# connection.net
KiCad netlist of a schematic drawn in Altium Designer
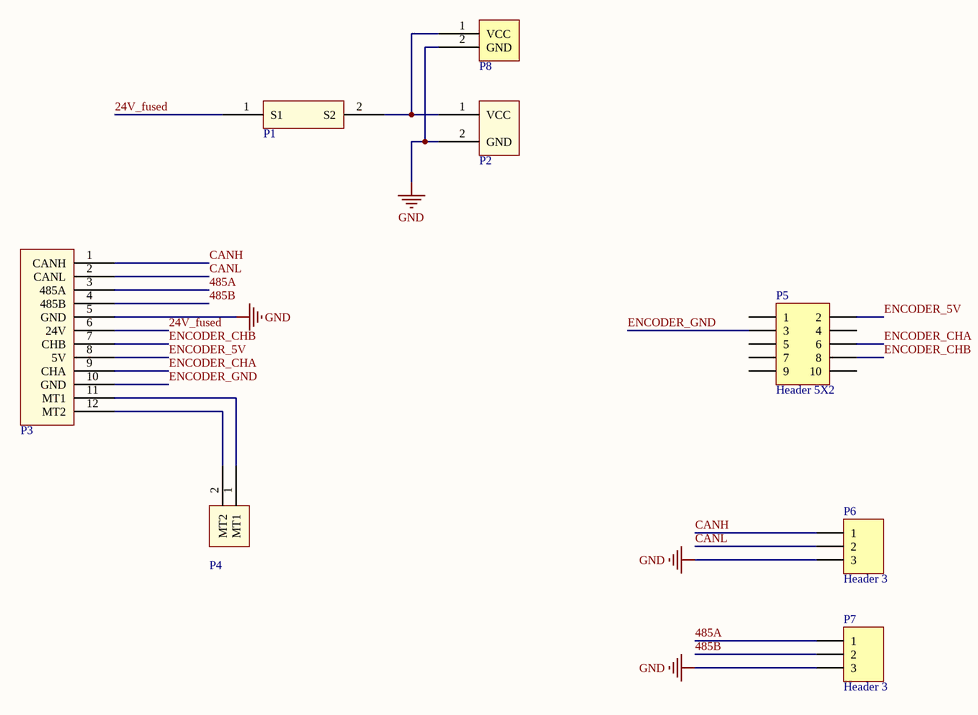
[diagram p0: connection.SchDoc]

(export (version "E")
  (design (tool "Eeschema 10.0.6"))
  (components
    (comp (ref "P1")
      (value "Car Fuse")
      (footprint "car_fuse")
      (libsource (lib "car_fuse") (part "Component_1"))
    )
    (comp (ref "P2")
      (value "big Pin power port")
      (footprint "bigPin_power_port")
      (libsource (lib "bigPin_power_port") (part "big Pin power port"))
    )
    (comp (ref "P3")
      (value "Robo Module Connector")
      (footprint "robomoduleConnector")
      (libsource (lib "robo_module_connector") (part "robomoduleConnector"))
    )
    (comp (ref "P4")
      (value "KF762-p_connector")
      (footprint "KF762")
      (libsource (lib "KF762connector") (part "KF762-p_connector"))
    )
    (comp (ref "P5")
      (value "Header 5X2")
      (footprint "HDR2X5")
      (description "Header, 5-Pin, Dual row")
      (fields (field (name "PUBLISHER") "Altium Limited"))
      (libsource (lib "Miscellaneous Connectors") (part "Header 5X2"))
    )
    (comp (ref "P6")
      (value "Header 3")
      (footprint "HDR1X3")
      (description "Header, 3-Pin")
      (fields (field (name "PUBLISHER") "Altium Limited"))
      (libsource (lib "Miscellaneous Connectors") (part "Header 3"))
    )
    (comp (ref "P7")
      (value "Header 3")
      (footprint "HDR1X3")
      (description "Header, 3-Pin")
      (fields (field (name "PUBLISHER") "Altium Limited"))
      (libsource (lib "Miscellaneous Connectors") (part "Header 3"))
    )
    (comp (ref "P8")
      (value "5557 Connector")
      (footprint "5557_connector")
      (libsource (lib "5557 connector") (part "5557_connector"))
    )
  )
  (nets
    (net (code "1") (name "/24V_fused") (class "Default")
      (node (ref "P1") (pin "1") (pinfunction "S1_1") (pintype "passive"))
      (node (ref "P3") (pin "6") (pinfunction "24V_6") (pintype "passive"))
    )
    (net (code "2") (name "/485A") (class "Default")
      (node (ref "P3") (pin "3") (pinfunction "485A_3") (pintype "passive"))
      (node (ref "P7") (pin "1") (pinfunction "1_1") (pintype "passive"))
    )
    (net (code "3") (name "/485B") (class "Default")
      (node (ref "P3") (pin "4") (pinfunction "485B_4") (pintype "passive"))
      (node (ref "P7") (pin "2") (pinfunction "2_2") (pintype "passive"))
    )
    (net (code "4") (name "/CANH") (class "Default")
      (node (ref "P3") (pin "1") (pinfunction "CANH_1") (pintype "passive"))
      (node (ref "P6") (pin "1") (pinfunction "1_1") (pintype "passive"))
    )
    (net (code "5") (name "/CANL") (class "Default")
      (node (ref "P3") (pin "2") (pinfunction "CANL_2") (pintype "passive"))
      (node (ref "P6") (pin "2") (pinfunction "2_2") (pintype "passive"))
    )
    (net (code "6") (name "/ENCODER_5V") (class "Default")
      (node (ref "P3") (pin "8") (pinfunction "5V_8") (pintype "passive"))
      (node (ref "P5") (pin "2") (pinfunction "2_2") (pintype "passive"))
    )
    (net (code "7") (name "/ENCODER_CHA") (class "Default")
      (node (ref "P3") (pin "9") (pinfunction "CHA_9") (pintype "passive"))
      (node (ref "P5") (pin "6") (pinfunction "6_6") (pintype "passive"))
    )
    (net (code "8") (name "/ENCODER_CHB") (class "Default")
      (node (ref "P3") (pin "7") (pinfunction "CHB_7") (pintype "passive"))
      (node (ref "P5") (pin "8") (pinfunction "8_8") (pintype "passive"))
    )
    (net (code "9") (name "/ENCODER_GND") (class "Default")
      (node (ref "P3") (pin "10") (pinfunction "GND_10") (pintype "passive"))
      (node (ref "P5") (pin "3") (pinfunction "3_3") (pintype "passive"))
    )
    (net (code "10") (name "GND") (class "Default")
      (node (ref "P2") (pin "2") (pinfunction "GND_2") (pintype "passive"))
      (node (ref "P3") (pin "5") (pinfunction "GND_5") (pintype "passive"))
      (node (ref "P6") (pin "3") (pinfunction "3_3") (pintype "passive"))
      (node (ref "P7") (pin "3") (pinfunction "3_3") (pintype "passive"))
      (node (ref "P8") (pin "2") (pinfunction "GND_2") (pintype "passive"))
    )
    (net (code "11") (name "Net-(P1-S2)") (class "Default")
      (node (ref "P1") (pin "2") (pinfunction "S2_2") (pintype "passive"))
      (node (ref "P2") (pin "1") (pinfunction "VCC_1") (pintype "passive"))
      (node (ref "P8") (pin "1") (pinfunction "VCC_1") (pintype "passive"))
    )
    (net (code "12") (name "Net-(P3-MT1)") (class "Default")
      (node (ref "P3") (pin "11") (pinfunction "MT1_11") (pintype "passive"))
      (node (ref "P4") (pin "1") (pinfunction "MT1_1") (pintype "passive"))
    )
    (net (code "13") (name "Net-(P3-MT2)") (class "Default")
      (node (ref "P3") (pin "12") (pinfunction "MT2_12") (pintype "passive"))
      (node (ref "P4") (pin "2") (pinfunction "MT2_2") (pintype "passive"))
    )
    (net (code "14") (name "unconnected-(P5-Pad1)") (class "Default")
      (node (ref "P5") (pin "1") (pinfunction "1_1") (pintype "passive"))
    )
    (net (code "15") (name "unconnected-(P5-Pad4)") (class "Default")
      (node (ref "P5") (pin "4") (pinfunction "4_4") (pintype "passive"))
    )
    (net (code "16") (name "unconnected-(P5-Pad5)") (class "Default")
      (node (ref "P5") (pin "5") (pinfunction "5_5") (pintype "passive"))
    )
    (net (code "17") (name "unconnected-(P5-Pad7)") (class "Default")
      (node (ref "P5") (pin "7") (pinfunction "7_7") (pintype "passive"))
    )
    (net (code "18") (name "unconnected-(P5-Pad9)") (class "Default")
      (node (ref "P5") (pin "9") (pinfunction "9_9") (pintype "passive"))
    )
    (net (code "19") (name "unconnected-(P5-Pad10)") (class "Default")
      (node (ref "P5") (pin "10") (pinfunction "10_10") (pintype "passive"))
    )
  )
)
